# uni2bi.net
KiCad netlist of a schematic drawn in EAGLE
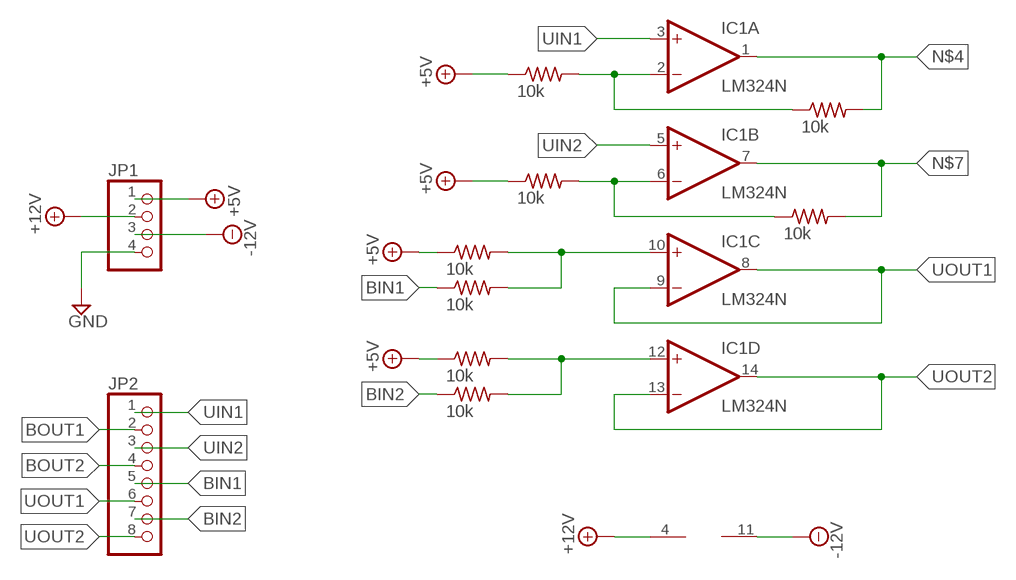
[diagram p0: schematic, sheet 1]

(export (version "E")
  (design (tool "Eeschema 10.0.6"))
  (components
    (comp (ref "IC1")
      (value "LM324N")
      (footprint "eagle-import:DIL14")
      (libsource (lib "eagle-import") (part "LM324N"))
    )
    (comp (ref "JP1")
      (value "PINHD-1X4")
      (footprint "eagle-import:1X04")
      (libsource (lib "eagle-import") (part "PINHD-1X4"))
    )
    (comp (ref "JP2")
      (value "PINHD-1X8")
      (footprint "eagle-import:1X08")
      (libsource (lib "eagle-import") (part "PINHD-1X8"))
    )
    (comp (ref "R3")
      (value "10k")
      (footprint "eagle-import:0207_10")
      (libsource (lib "eagle-import") (part "R-US_0207/10"))
    )
    (comp (ref "R4")
      (value "10k")
      (footprint "eagle-import:0207_10")
      (libsource (lib "eagle-import") (part "R-US_0207/10"))
    )
    (comp (ref "R5")
      (value "10k")
      (footprint "eagle-import:0207_10")
      (libsource (lib "eagle-import") (part "R-US_0207/10"))
    )
    (comp (ref "R6")
      (value "10k")
      (footprint "eagle-import:0207_10")
      (libsource (lib "eagle-import") (part "R-US_0207/10"))
    )
    (comp (ref "R7")
      (value "10k")
      (footprint "eagle-import:0207_10")
      (libsource (lib "eagle-import") (part "R-US_0207/10"))
    )
    (comp (ref "R8")
      (value "10k")
      (footprint "eagle-import:0207_10")
      (libsource (lib "eagle-import") (part "R-US_0207/10"))
    )
    (comp (ref "R9")
      (value "10k")
      (footprint "eagle-import:0207_10")
      (libsource (lib "eagle-import") (part "R-US_0207/10"))
    )
    (comp (ref "R10")
      (value "10k")
      (footprint "eagle-import:0207_10")
      (libsource (lib "eagle-import") (part "R-US_0207/10"))
    )
  )
  (nets
    (net (code "1") (name "+5V") (class "Default")
      (node (ref "JP1") (pin "1") (pinfunction "1_1") (pintype "passive"))
      (node (ref "R3") (pin "1") (pinfunction "1_1") (pintype "passive"))
      (node (ref "R7") (pin "1") (pinfunction "1_1") (pintype "passive"))
      (node (ref "R8") (pin "1") (pinfunction "1_1") (pintype "passive"))
      (node (ref "R9") (pin "1") (pinfunction "1_1") (pintype "passive"))
    )
    (net (code "2") (name "+12V") (class "Default")
      (node (ref "IC1") (pin "4") (pinfunction "V+_4") (pintype "power_in"))
      (node (ref "JP1") (pin "2") (pinfunction "2_2") (pintype "passive"))
    )
    (net (code "3") (name "-12V") (class "Default")
      (node (ref "IC1") (pin "11") (pinfunction "V-_11") (pintype "power_in"))
      (node (ref "JP1") (pin "3") (pinfunction "3_3") (pintype "passive"))
    )
    (net (code "4") (name "BIN1") (class "Default")
      (node (ref "JP2") (pin "5") (pinfunction "5_5") (pintype "passive"))
      (node (ref "R4") (pin "1") (pinfunction "1_1") (pintype "passive"))
    )
    (net (code "5") (name "BIN2") (class "Default")
      (node (ref "JP2") (pin "7") (pinfunction "7_7") (pintype "passive"))
      (node (ref "R5") (pin "1") (pinfunction "1_1") (pintype "passive"))
    )
    (net (code "6") (name "BOUT1") (class "Default")
      (node (ref "IC1") (pin "2") (pinfunction "-IN_2") (pintype "input"))
      (node (ref "JP2") (pin "2") (pinfunction "2_2") (pintype "passive"))
      (node (ref "R10") (pin "1") (pinfunction "1_1") (pintype "passive"))
      (node (ref "R8") (pin "2") (pinfunction "2_2") (pintype "passive"))
    )
    (net (code "7") (name "BOUT2") (class "Default")
      (node (ref "IC1") (pin "6") (pinfunction "-IN_6") (pintype "input"))
      (node (ref "JP2") (pin "4") (pinfunction "4_4") (pintype "passive"))
      (node (ref "R6") (pin "1") (pinfunction "1_1") (pintype "passive"))
      (node (ref "R7") (pin "2") (pinfunction "2_2") (pintype "passive"))
    )
    (net (code "8") (name "GND") (class "Default")
      (node (ref "JP1") (pin "4") (pinfunction "4_4") (pintype "passive"))
    )
    (net (code "9") (name "N$4") (class "Default")
      (node (ref "IC1") (pin "1") (pinfunction "OUT_1") (pintype "output"))
      (node (ref "R10") (pin "2") (pinfunction "2_2") (pintype "passive"))
    )
    (net (code "10") (name "N$7") (class "Default")
      (node (ref "IC1") (pin "7") (pinfunction "OUT_7") (pintype "output"))
      (node (ref "R6") (pin "2") (pinfunction "2_2") (pintype "passive"))
    )
    (net (code "11") (name "Net-(IC1C-+IN)") (class "Default")
      (node (ref "IC1") (pin "10") (pinfunction "+IN_10") (pintype "input"))
      (node (ref "R4") (pin "2") (pinfunction "2_2") (pintype "passive"))
      (node (ref "R9") (pin "2") (pinfunction "2_2") (pintype "passive"))
    )
    (net (code "12") (name "Net-(IC1D-+IN)") (class "Default")
      (node (ref "IC1") (pin "12") (pinfunction "+IN_12") (pintype "input"))
      (node (ref "R3") (pin "2") (pinfunction "2_2") (pintype "passive"))
      (node (ref "R5") (pin "2") (pinfunction "2_2") (pintype "passive"))
    )
    (net (code "13") (name "UIN1") (class "Default")
      (node (ref "IC1") (pin "3") (pinfunction "+IN_3") (pintype "input"))
      (node (ref "JP2") (pin "1") (pinfunction "1_1") (pintype "passive"))
    )
    (net (code "14") (name "UIN2") (class "Default")
      (node (ref "IC1") (pin "5") (pinfunction "+IN_5") (pintype "input"))
      (node (ref "JP2") (pin "3") (pinfunction "3_3") (pintype "passive"))
    )
    (net (code "15") (name "UOUT1") (class "Default")
      (node (ref "IC1") (pin "8") (pinfunction "OUT_8") (pintype "output"))
      (node (ref "IC1") (pin "9") (pinfunction "-IN_9") (pintype "input"))
      (node (ref "JP2") (pin "6") (pinfunction "6_6") (pintype "passive"))
    )
    (net (code "16") (name "UOUT2") (class "Default")
      (node (ref "IC1") (pin "13") (pinfunction "-IN_13") (pintype "input"))
      (node (ref "IC1") (pin "14") (pinfunction "OUT_14") (pintype "output"))
      (node (ref "JP2") (pin "8") (pinfunction "8_8") (pintype "passive"))
    )
  )
)
